# UKU100P.net
KiCad netlist of a schematic drawn in Altium Designer
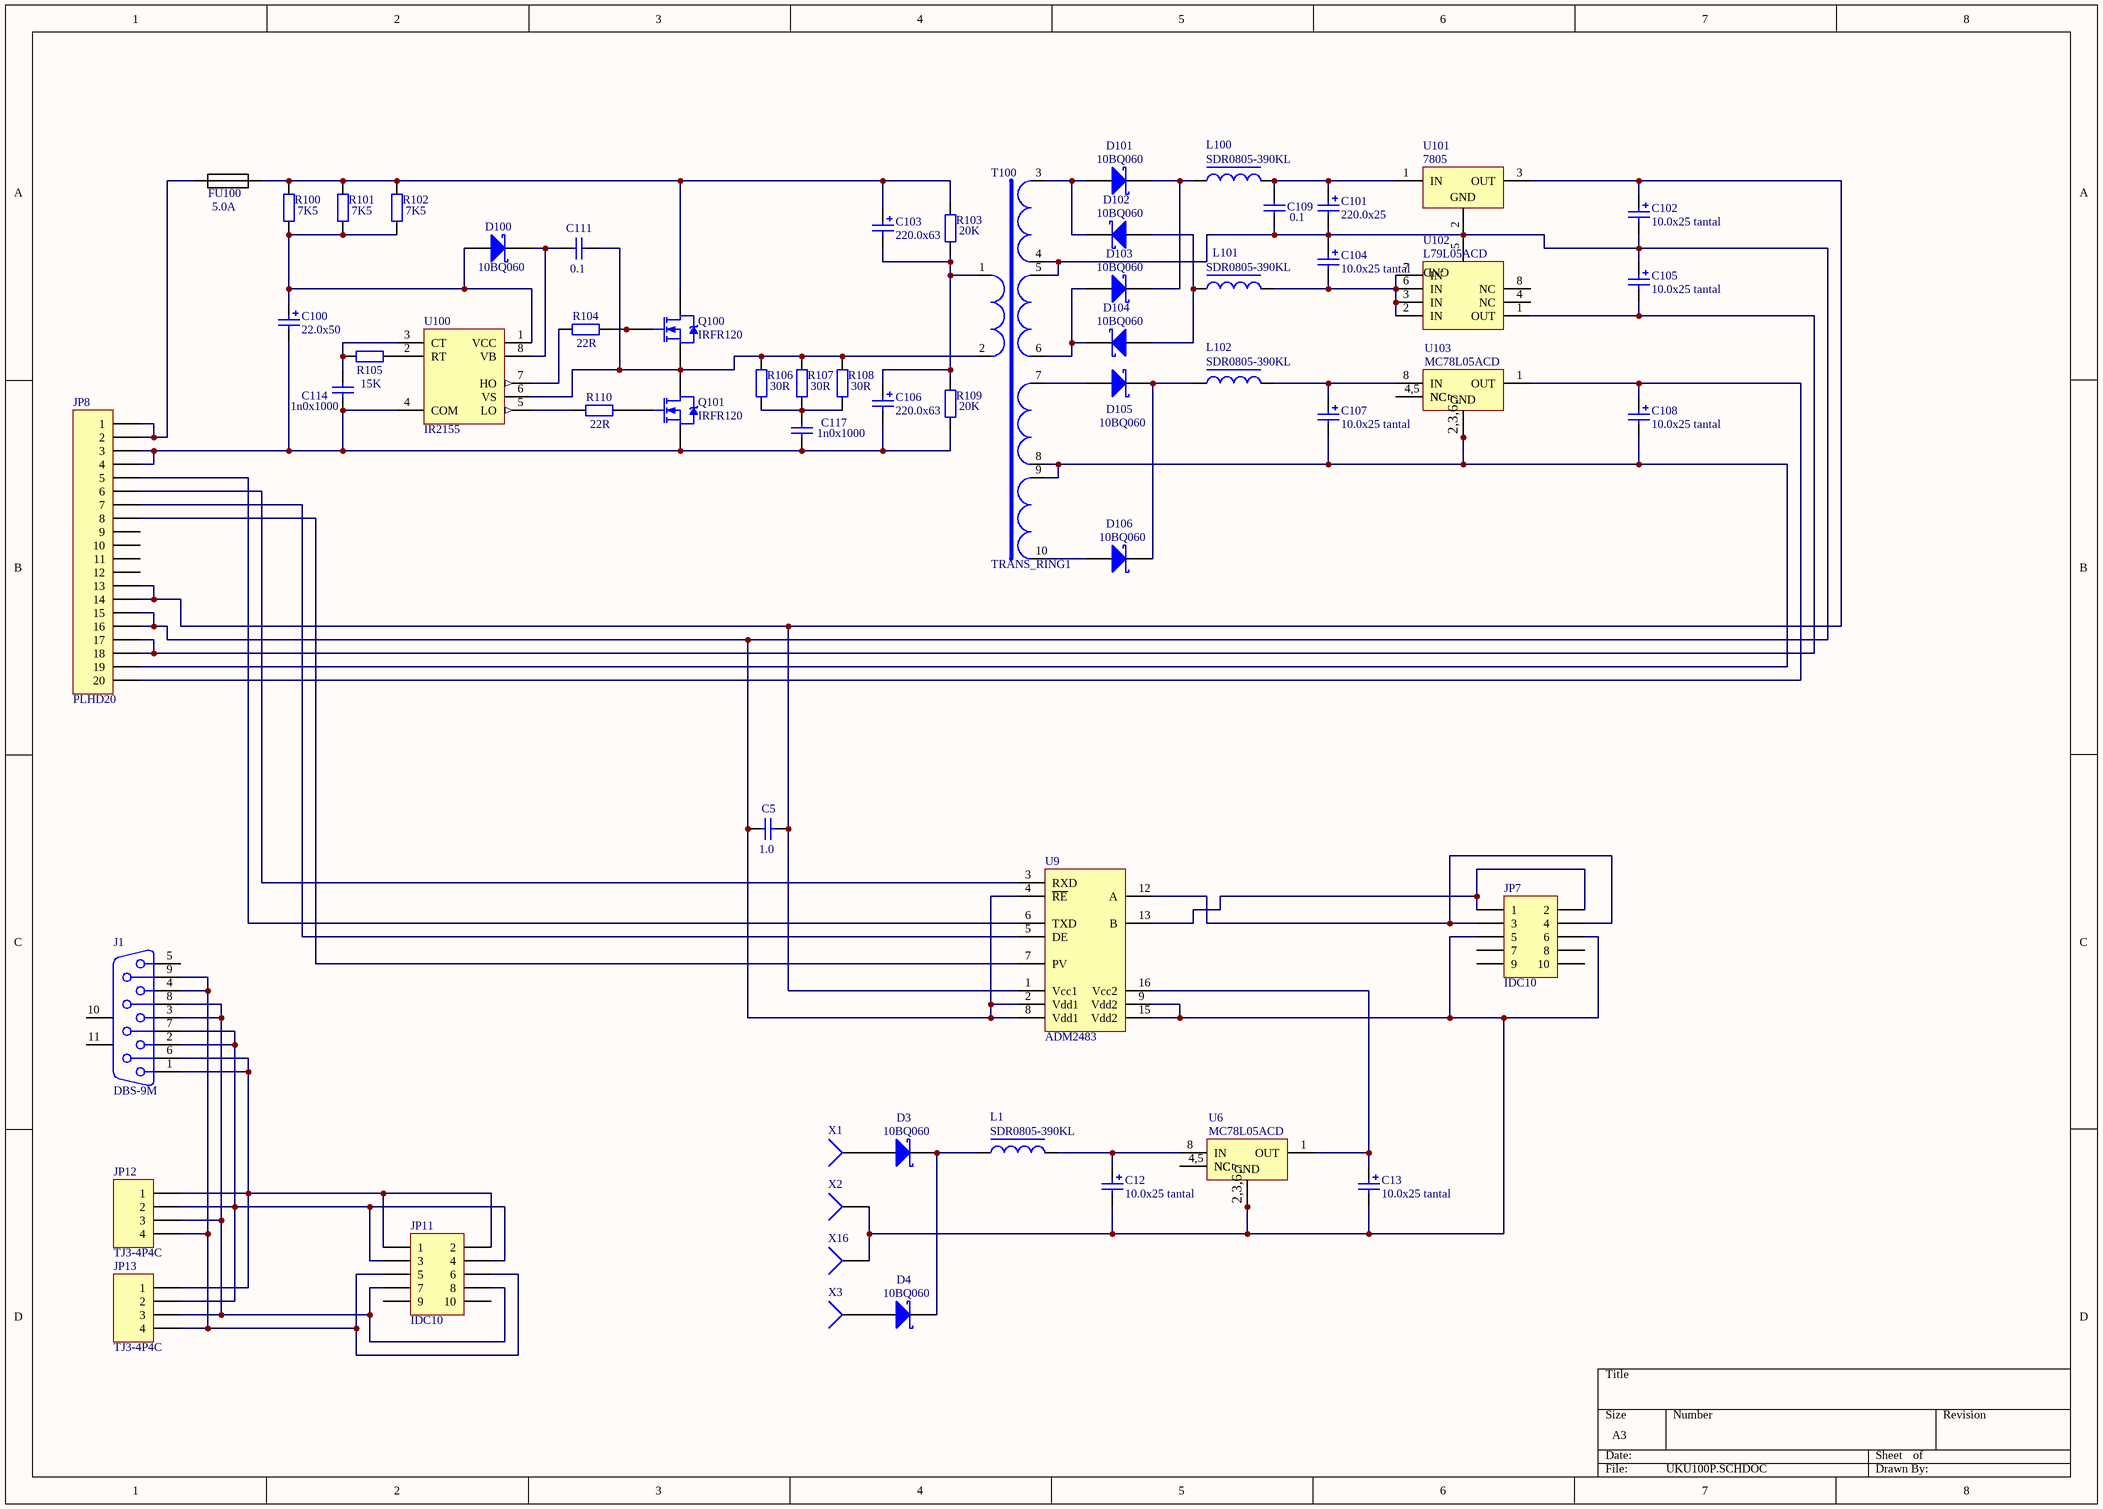
[diagram p0: UKU100P.SCHDOC]

(export (version "E")
  (design (tool "Eeschema 10.0.6"))
  (components
    (comp (ref "C5")
      (value "1.0")
      (footprint "C3216-1206")
      (description "Capacitor (Semiconductor SIM Model)")
      (fields (field (name "MANUFACTURER") "Generic Components") (field (name "PUBLISHER") "Altium Limited"))
      (libsource (lib "Miscellaneous Devices") (part "Cap Semi"))
    )
    (comp (ref "C12")
      (value "10.0x25 tantal")
      (footprint "CAP_EL_6_3")
      (description "Polarized Capacitor (Radial)")
      (fields (field (name "MANUFACTURER") "Generic Components") (field (name "PUBLISHER") "Altium Limited"))
      (libsource (lib "PAL") (part "Cap Pol1"))
    )
    (comp (ref "C13")
      (value "10.0x25 tantal")
      (footprint "CAP_EL_6_3")
      (description "Polarized Capacitor (Radial)")
      (fields (field (name "MANUFACTURER") "Generic Components") (field (name "PUBLISHER") "Altium Limited"))
      (libsource (lib "PAL") (part "Cap Pol1"))
    )
    (comp (ref "C100")
      (value "22.0x50")
      (footprint "el3")
      (description "Polarized Capacitor (Radial)")
      (fields (field (name "MANUFACTURER") "Generic Components") (field (name "PUBLISHER") "Altium Limited"))
      (libsource (lib "PAL") (part "Cap Pol1"))
    )
    (comp (ref "C101")
      (value "220.0x25")
      (footprint "el5")
      (description "Polarized Capacitor (Radial)")
      (fields (field (name "MANUFACTURER") "Generic Components") (field (name "PUBLISHER") "Altium Limited"))
      (libsource (lib "PAL") (part "Cap Pol1"))
    )
    (comp (ref "C102")
      (value "10.0x25 tantal")
      (footprint "CAP_EL_6_3")
      (description "Polarized Capacitor (Radial)")
      (fields (field (name "MANUFACTURER") "Generic Components") (field (name "PUBLISHER") "Altium Limited"))
      (libsource (lib "PAL") (part "Cap Pol1"))
    )
    (comp (ref "C103")
      (value "220.0x63")
      (footprint "el5")
      (description "Polarized Capacitor (Radial)")
      (fields (field (name "MANUFACTURER") "Generic Components") (field (name "PUBLISHER") "Altium Limited"))
      (libsource (lib "PAL") (part "Cap Pol1"))
    )
    (comp (ref "C104")
      (value "10.0x25 tantal")
      (footprint "CAP_EL_6_3")
      (description "Polarized Capacitor (Radial)")
      (fields (field (name "MANUFACTURER") "Generic Components") (field (name "PUBLISHER") "Altium Limited"))
      (libsource (lib "PAL") (part "Cap Pol1"))
    )
    (comp (ref "C105")
      (value "10.0x25 tantal")
      (footprint "CAP_EL_6_3")
      (description "Polarized Capacitor (Radial)")
      (fields (field (name "MANUFACTURER") "Generic Components") (field (name "PUBLISHER") "Altium Limited"))
      (libsource (lib "PAL") (part "Cap Pol1"))
    )
    (comp (ref "C106")
      (value "220.0x63")
      (footprint "el5")
      (description "Polarized Capacitor (Radial)")
      (fields (field (name "MANUFACTURER") "Generic Components") (field (name "PUBLISHER") "Altium Limited"))
      (libsource (lib "PAL") (part "Cap Pol1"))
    )
    (comp (ref "C107")
      (value "10.0x25 tantal")
      (footprint "CAP_EL_6_3")
      (description "Polarized Capacitor (Radial)")
      (fields (field (name "MANUFACTURER") "Generic Components") (field (name "PUBLISHER") "Altium Limited"))
      (libsource (lib "PAL") (part "Cap Pol1"))
    )
    (comp (ref "C108")
      (value "10.0x25 tantal")
      (footprint "CAP_EL_6_3")
      (description "Polarized Capacitor (Radial)")
      (fields (field (name "MANUFACTURER") "Generic Components") (field (name "PUBLISHER") "Altium Limited"))
      (libsource (lib "PAL") (part "Cap Pol1"))
    )
    (comp (ref "C109")
      (value "0.1")
      (footprint "C3216-1206")
      (description "Capacitor (Semiconductor SIM Model)")
      (fields (field (name "MANUFACTURER") "Generic Components") (field (name "PUBLISHER") "Altium Limited"))
      (libsource (lib "Miscellaneous Devices") (part "Cap Semi"))
    )
    (comp (ref "C111")
      (value "0.1")
      (footprint "C3216-1206")
      (description "Capacitor (Semiconductor SIM Model)")
      (fields (field (name "MANUFACTURER") "Generic Components") (field (name "PUBLISHER") "Altium Limited"))
      (libsource (lib "Miscellaneous Devices") (part "Cap Semi"))
    )
    (comp (ref "C114")
      (value "1n0x1000")
      (footprint "C3216-1206")
      (description "Capacitor (Semiconductor SIM Model)")
      (fields (field (name "MANUFACTURER") "Generic Components") (field (name "PUBLISHER") "Altium Limited"))
      (libsource (lib "Miscellaneous Devices") (part "Cap Semi"))
    )
    (comp (ref "C117")
      (value "1n0x1000")
      (footprint "C3216-1206")
      (description "Capacitor (Semiconductor SIM Model)")
      (fields (field (name "MANUFACTURER") "Generic Components") (field (name "PUBLISHER") "Altium Limited"))
      (libsource (lib "Miscellaneous Devices") (part "Cap Semi"))
    )
    (comp (ref "D3")
      (value "10BQ060")
      (footprint "DSO-C2/X2.3")
      (description "Schottky Rectifier")
      (fields
        (field (name "MANUFACTURER") "International Rectifier")
        (field (name "PUBLISHER") "Altium Limited")
      )
      (libsource (lib "IR Discrete Diode") (part "10BQ015"))
    )
    (comp (ref "D4")
      (value "10BQ060")
      (footprint "DSO-C2/X2.3")
      (description "Schottky Rectifier")
      (fields
        (field (name "MANUFACTURER") "International Rectifier")
        (field (name "PUBLISHER") "Altium Limited")
      )
      (libsource (lib "IR Discrete Diode") (part "10BQ015"))
    )
    (comp (ref "D100")
      (value "10BQ060")
      (footprint "DSO-C2/X2.3")
      (description "Schottky Rectifier")
      (fields
        (field (name "MANUFACTURER") "International Rectifier")
        (field (name "PUBLISHER") "Altium Limited")
      )
      (libsource (lib "IR Discrete Diode") (part "10BQ015"))
    )
    (comp (ref "D101")
      (value "10BQ060")
      (footprint "D_6_3")
      (description "Schottky Rectifier")
      (fields
        (field (name "MANUFACTURER") "International Rectifier")
        (field (name "PUBLISHER") "Altium Limited")
      )
      (libsource (lib "IR Discrete Diode") (part "10BQ015"))
    )
    (comp (ref "D102")
      (value "10BQ060")
      (footprint "D_6_3")
      (description "Schottky Rectifier")
      (fields
        (field (name "MANUFACTURER") "International Rectifier")
        (field (name "PUBLISHER") "Altium Limited")
      )
      (libsource (lib "IR Discrete Diode") (part "10BQ015"))
    )
    (comp (ref "D103")
      (value "10BQ060")
      (footprint "D_6_3")
      (description "Schottky Rectifier")
      (fields
        (field (name "MANUFACTURER") "International Rectifier")
        (field (name "PUBLISHER") "Altium Limited")
      )
      (libsource (lib "IR Discrete Diode") (part "10BQ015"))
    )
    (comp (ref "D104")
      (value "10BQ060")
      (footprint "D_6_3")
      (description "Schottky Rectifier")
      (fields
        (field (name "MANUFACTURER") "International Rectifier")
        (field (name "PUBLISHER") "Altium Limited")
      )
      (libsource (lib "IR Discrete Diode") (part "10BQ015"))
    )
    (comp (ref "D105")
      (value "10BQ060")
      (footprint "DSO-C2/X2.3")
      (description "Schottky Rectifier")
      (fields
        (field (name "MANUFACTURER") "International Rectifier")
        (field (name "PUBLISHER") "Altium Limited")
      )
      (libsource (lib "IR Discrete Diode") (part "10BQ015"))
    )
    (comp (ref "D106")
      (value "10BQ060")
      (footprint "DSO-C2/X2.3")
      (description "Schottky Rectifier")
      (fields
        (field (name "MANUFACTURER") "International Rectifier")
        (field (name "PUBLISHER") "Altium Limited")
      )
      (libsource (lib "IR Discrete Diode") (part "10BQ015"))
    )
    (comp (ref "FU100") (value "5.0A") (footprint "FUSE2") (libsource (lib "PAL") (part "FUSE")))
    (comp (ref "J1")
      (value "DBS-9M")
      (footprint "DSUB_N9")
      (description "Receptacle Assembly, 9 Position, Right Angle")
      (fields (field (name "MANUFACTURER") "Generic Components") (field (name "PUBLISHER") "Altium Limited"))
      (libsource (lib "Miscellaneous Connectors") (part "D Connector 9"))
    )
    (comp (ref "JP7")
      (value "IDC10")
      (footprint "HDR2X5")
      (description "Header, 5-Pin, Dual row")
      (fields (field (name "MANUFACTURER") "Generic Components") (field (name "PUBLISHER") "Altium Limited"))
      (libsource (lib "Miscellaneous Connectors") (part "Header 5X2"))
    )
    (comp (ref "JP8")
      (value "PLHD20")
      (footprint "HDR2X10")
      (description "Header, 20-Pin")
      (fields (field (name "MANUFACTURER") "Generic Components") (field (name "PUBLISHER") "Altium Limited"))
      (libsource (lib "Miscellaneous Connectors") (part "Header 20"))
    )
    (comp (ref "JP11")
      (value "IDC10")
      (footprint "HDR2X5")
      (description "Header, 5-Pin, Dual row")
      (fields (field (name "MANUFACTURER") "Generic Components") (field (name "PUBLISHER") "Altium Limited"))
      (libsource (lib "Miscellaneous Connectors") (part "Header 5X2"))
    )
    (comp (ref "JP12")
      (value "TJ3-4P4C")
      (footprint "tj3-4p4c")
      (description "Header, 4-Pin")
      (fields (field (name "MANUFACTURER") "Generic Components") (field (name "PUBLISHER") "Altium Limited"))
      (libsource (lib "Miscellaneous Connectors") (part "Header 4"))
    )
    (comp (ref "JP13")
      (value "TJ3-4P4C")
      (footprint "tj3-4p4c")
      (description "Header, 4-Pin")
      (fields (field (name "MANUFACTURER") "Generic Components") (field (name "PUBLISHER") "Altium Limited"))
      (libsource (lib "Miscellaneous Connectors") (part "Header 4"))
    )
    (comp (ref "L1")
      (value "SDR0805-390KL")
      (footprint "L10x10")
      (description "Magnetic-Core Inductor")
      (fields (field (name "MANUFACTURER") "Generic Components") (field (name "PUBLISHER") "Altium Limited"))
      (libsource (lib "PAL") (part "Inductor Konstr 2"))
    )
    (comp (ref "L100")
      (value "SDR0805-390KL")
      (footprint "L10x10")
      (description "Magnetic-Core Inductor")
      (fields (field (name "MANUFACTURER") "Generic Components") (field (name "PUBLISHER") "Altium Limited"))
      (libsource (lib "PAL") (part "Inductor Konstr 2"))
    )
    (comp (ref "L101")
      (value "SDR0805-390KL")
      (footprint "L10x10")
      (description "Magnetic-Core Inductor")
      (fields (field (name "MANUFACTURER") "Generic Components") (field (name "PUBLISHER") "Altium Limited"))
      (libsource (lib "PAL") (part "Inductor Konstr 2"))
    )
    (comp (ref "L102")
      (value "SDR0805-390KL")
      (footprint "L10x10")
      (description "Magnetic-Core Inductor")
      (fields (field (name "MANUFACTURER") "Generic Components") (field (name "PUBLISHER") "Altium Limited"))
      (libsource (lib "PAL") (part "Inductor Konstr 2"))
    )
    (comp (ref "Q100")
      (value "IRFR120")
      (footprint "SIP-G3/E8")
      (description "HEXFET N-Channel Power MOSFET")
      (fields
        (field (name "MANUFACTURER") "International Rectifier")
        (field (name "PUBLISHER") "Altium Limited")
      )
      (libsource (lib "IR Discrete MOSFET") (part "IRFR120"))
    )
    (comp (ref "Q101")
      (value "IRFR120")
      (footprint "SIP-G3/E8")
      (description "HEXFET N-Channel Power MOSFET")
      (fields
        (field (name "MANUFACTURER") "International Rectifier")
        (field (name "PUBLISHER") "Altium Limited")
      )
      (libsource (lib "IR Discrete MOSFET") (part "IRFR120"))
    )
    (comp (ref "R100")
      (value "7K5")
      (footprint "_1206")
      (description "Resistor")
      (fields (field (name "MANUFACTURER") "Generic Components") (field (name "PUBLISHER") "Altium Limited"))
      (libsource (lib "") (part "Res2_1"))
    )
    (comp (ref "R101")
      (value "7K5")
      (footprint "_1206")
      (description "Resistor")
      (fields (field (name "MANUFACTURER") "Generic Components") (field (name "PUBLISHER") "Altium Limited"))
      (libsource (lib "") (part "Res2_1"))
    )
    (comp (ref "R102")
      (value "7K5")
      (footprint "_1206")
      (description "Resistor")
      (fields (field (name "MANUFACTURER") "Generic Components") (field (name "PUBLISHER") "Altium Limited"))
      (libsource (lib "") (part "Res2_1"))
    )
    (comp (ref "R103")
      (value "20K")
      (footprint "_1206")
      (description "Resistor")
      (fields (field (name "MANUFACTURER") "Generic Components") (field (name "PUBLISHER") "Altium Limited"))
      (libsource (lib "") (part "Res2_1"))
    )
    (comp (ref "R104")
      (value "22R")
      (footprint "_1206")
      (description "Resistor")
      (fields (field (name "MANUFACTURER") "Generic Components") (field (name "PUBLISHER") "Altium Limited"))
      (libsource (lib "Miscellaneous Devices") (part "Res2"))
    )
    (comp (ref "R105")
      (value "15K")
      (footprint "_1206")
      (description "Resistor")
      (fields (field (name "MANUFACTURER") "Generic Components") (field (name "PUBLISHER") "Altium Limited"))
      (libsource (lib "Miscellaneous Devices") (part "Res2"))
    )
    (comp (ref "R106")
      (value "30R")
      (footprint "_1206")
      (description "Resistor")
      (fields (field (name "MANUFACTURER") "Generic Components") (field (name "PUBLISHER") "Altium Limited"))
      (libsource (lib "") (part "Res2_1"))
    )
    (comp (ref "R107")
      (value "30R")
      (footprint "_1206")
      (description "Resistor")
      (fields (field (name "MANUFACTURER") "Generic Components") (field (name "PUBLISHER") "Altium Limited"))
      (libsource (lib "") (part "Res2_1"))
    )
    (comp (ref "R108")
      (value "30R")
      (footprint "_1206")
      (description "Resistor")
      (fields (field (name "MANUFACTURER") "Generic Components") (field (name "PUBLISHER") "Altium Limited"))
      (libsource (lib "") (part "Res2_1"))
    )
    (comp (ref "R109")
      (value "20K")
      (footprint "_1206")
      (description "Resistor")
      (fields (field (name "MANUFACTURER") "Generic Components") (field (name "PUBLISHER") "Altium Limited"))
      (libsource (lib "") (part "Res2_1"))
    )
    (comp (ref "R110")
      (value "22R")
      (footprint "_1206")
      (description "Resistor")
      (fields (field (name "MANUFACTURER") "Generic Components") (field (name "PUBLISHER") "Altium Limited"))
      (libsource (lib "Miscellaneous Devices") (part "Res2"))
    )
    (comp (ref "T100")
      (value "TRANS_RING1")
      (footprint "trans_ring1")
      (libsource (lib "PAL") (part "TRANS_RING1"))
    )
    (comp (ref "U6")
      (value "MC78L05ACD")
      (footprint "SO-G8")
      (description "3-Terminal Low-Current Positive Fixed Voltage Regulator")
      (fields (field (name "MANUFACTURER") "Motorola") (field (name "PUBLISHER") "Altium Limited"))
      (libsource (lib "Motorola Power Management Voltage Regulator") (part "MC78L05ACD"))
    )
    (comp (ref "U9") (value "ADM2483") (footprint "SO-G16/D10.4") (libsource (lib "PAL") (part "ADM2483")))
    (comp (ref "U100")
      (value "IR2155")
      (footprint "DIP-8/D11")
      (description "Self-Oscillating Half-Bridge Driver")
      (fields
        (field (name "MANUFACTURER") "International Rectifier")
        (field (name "PUBLISHER") "Altium Limited")
      )
      (libsource (lib "IR Interface Bridge Driver") (part "IR2155"))
    )
    (comp (ref "U101")
      (value "7805")
      (footprint "7805_1")
      (description "3-Terminal Positive Fixed Voltage Regulator")
      (fields (field (name "MANUFACTURER") "Motorola") (field (name "PUBLISHER") "Altium Limited"))
      (libsource (lib "PAL") (part "7805"))
    )
    (comp (ref "U102")
      (value "L79L05ACD")
      (footprint "SO-G8")
      (description "Negative Voltage Regulator")
      (fields (field (name "MANUFACTURER") "ST-Microelectronics") (field (name "PUBLISHER") "Altium Limited"))
      (libsource (lib "ST Power Mgt Voltage Regulator") (part "L79L05ACD"))
    )
    (comp (ref "U103")
      (value "MC78L05ACD")
      (footprint "SO-G8")
      (description "3-Terminal Low-Current Positive Fixed Voltage Regulator")
      (fields (field (name "MANUFACTURER") "Motorola") (field (name "PUBLISHER") "Altium Limited"))
      (libsource (lib "Motorola Power Management Voltage Regulator") (part "MC78L05ACD"))
    )
    (comp (ref "X1")
      (value "~")
      (footprint "PIN1")
      (description "Socket")
      (fields (field (name "MANUFACTURER") "Generic Components") (field (name "PUBLISHER") "Altium Limited"))
      (libsource (lib "Miscellaneous Connectors") (part "Socket"))
    )
    (comp (ref "X2")
      (value "~")
      (footprint "PIN1")
      (description "Socket")
      (fields (field (name "MANUFACTURER") "Generic Components") (field (name "PUBLISHER") "Altium Limited"))
      (libsource (lib "Miscellaneous Connectors") (part "Socket"))
    )
    (comp (ref "X3")
      (value "~")
      (footprint "PIN1")
      (description "Socket")
      (fields (field (name "MANUFACTURER") "Generic Components") (field (name "PUBLISHER") "Altium Limited"))
      (libsource (lib "Miscellaneous Connectors") (part "Socket"))
    )
    (comp (ref "X16")
      (value "~")
      (footprint "PIN1")
      (description "Socket")
      (fields (field (name "MANUFACTURER") "Generic Components") (field (name "PUBLISHER") "Altium Limited"))
      (libsource (lib "Miscellaneous Connectors") (part "Socket"))
    )
  )
  (nets
    (net (code "1") (name "Net-(C12-Pad2)") (class "Default")
      (node (ref "C12") (pin "2") (pinfunction "2_2") (pintype "passive"))
      (node (ref "C13") (pin "2") (pinfunction "2_2") (pintype "passive"))
      (node (ref "JP7") (pin "5") (pinfunction "5_5") (pintype "passive"))
      (node (ref "JP7") (pin "6") (pinfunction "6_6") (pintype "passive"))
      (node (ref "U6") (pin "2") (pinfunction "GND_2") (pintype "power_in"))
      (node (ref "U6") (pin "3") (pinfunction "GND_3") (pintype "power_in"))
      (node (ref "U6") (pin "6") (pinfunction "GND_6") (pintype "power_in"))
      (node (ref "U6") (pin "7") (pinfunction "GND_7") (pintype "power_in"))
      (node (ref "U9") (pin "15") (pinfunction "Vdd2_15") (pintype "passive"))
      (node (ref "U9") (pin "9") (pinfunction "Vdd2_9") (pintype "passive"))
      (node (ref "X16") (pin "1") (pinfunction "1_1") (pintype "passive"))
      (node (ref "X2") (pin "1") (pinfunction "1_1") (pintype "passive"))
    )
    (net (code "2") (name "Net-(C103-Pad2)") (class "Default")
      (node (ref "C103") (pin "2") (pinfunction "2_2") (pintype "passive"))
      (node (ref "C106") (pin "1") (pinfunction "1_1") (pintype "passive"))
      (node (ref "R103") (pin "2") (pinfunction "2_2") (pintype "passive"))
      (node (ref "R109") (pin "1") (pinfunction "1_1") (pintype "passive"))
      (node (ref "T100") (pin "1") (pinfunction "Vss_1") (pintype "passive"))
    )
    (net (code "3") (name "Net-(C104-Pad2)") (class "Default")
      (node (ref "C104") (pin "2") (pinfunction "2_2") (pintype "passive"))
      (node (ref "L101") (pin "2") (pinfunction "2_2") (pintype "passive"))
      (node (ref "U102") (pin "2") (pinfunction "IN_2") (pintype "power_in"))
      (node (ref "U102") (pin "3") (pinfunction "IN_3") (pintype "power_in"))
      (node (ref "U102") (pin "6") (pinfunction "IN_6") (pintype "power_in"))
      (node (ref "U102") (pin "7") (pinfunction "IN_7") (pintype "power_in"))
    )
    (net (code "4") (name "Net-(C107-Pad2)") (class "Default")
      (node (ref "C107") (pin "2") (pinfunction "2_2") (pintype "passive"))
      (node (ref "C108") (pin "2") (pinfunction "2_2") (pintype "passive"))
      (node (ref "JP8") (pin "19") (pinfunction "19_19") (pintype "passive"))
      (node (ref "T100") (pin "8") (pinfunction "Vss_8") (pintype "passive"))
      (node (ref "T100") (pin "9") (pinfunction "Vss_9") (pintype "passive"))
      (node (ref "U103") (pin "2") (pinfunction "GND_2") (pintype "power_in"))
      (node (ref "U103") (pin "3") (pinfunction "GND_3") (pintype "power_in"))
      (node (ref "U103") (pin "6") (pinfunction "GND_6") (pintype "power_in"))
      (node (ref "U103") (pin "7") (pinfunction "GND_7") (pintype "power_in"))
    )
    (net (code "5") (name "Net-(C117-Pad1)") (class "Default")
      (node (ref "C117") (pin "1") (pinfunction "1_1") (pintype "passive"))
      (node (ref "R106") (pin "2") (pinfunction "2_2") (pintype "passive"))
      (node (ref "R107") (pin "2") (pinfunction "2_2") (pintype "passive"))
      (node (ref "R108") (pin "2") (pinfunction "2_2") (pintype "passive"))
    )
    (net (code "6") (name "Net-(D3-A)") (class "Default")
      (node (ref "D3") (pin "1") (pinfunction "A_1") (pintype "passive"))
      (node (ref "X1") (pin "1") (pinfunction "1_1") (pintype "passive"))
    )
    (net (code "7") (name "Net-(D3-K)") (class "Default")
      (node (ref "D3") (pin "2") (pinfunction "K_2") (pintype "passive"))
      (node (ref "D4") (pin "2") (pinfunction "K_2") (pintype "passive"))
      (node (ref "L1") (pin "1") (pinfunction "1_1") (pintype "passive"))
    )
    (net (code "8") (name "Net-(D4-A)") (class "Default")
      (node (ref "D4") (pin "1") (pinfunction "A_1") (pintype "passive"))
      (node (ref "X3") (pin "1") (pinfunction "1_1") (pintype "passive"))
    )
    (net (code "9") (name "Net-(D100-A)") (class "Default")
      (node (ref "C100") (pin "1") (pinfunction "1_1") (pintype "passive"))
      (node (ref "D100") (pin "1") (pinfunction "A_1") (pintype "passive"))
      (node (ref "R100") (pin "2") (pinfunction "2_2") (pintype "passive"))
      (node (ref "R101") (pin "2") (pinfunction "2_2") (pintype "passive"))
      (node (ref "R102") (pin "2") (pinfunction "2_2") (pintype "passive"))
      (node (ref "U100") (pin "1") (pinfunction "VCC_1") (pintype "power_in"))
    )
    (net (code "10") (name "Net-(D100-K)") (class "Default")
      (node (ref "C111") (pin "1") (pinfunction "1_1") (pintype "passive"))
      (node (ref "D100") (pin "2") (pinfunction "K_2") (pintype "passive"))
      (node (ref "U100") (pin "8") (pinfunction "VB_8") (pintype "power_in"))
    )
    (net (code "11") (name "Net-(D101-A)") (class "Default")
      (node (ref "D101") (pin "1") (pinfunction "A_1") (pintype "passive"))
      (node (ref "D102") (pin "2") (pinfunction "K_2") (pintype "passive"))
      (node (ref "T100") (pin "3") (pinfunction "Vss_3") (pintype "passive"))
    )
    (net (code "12") (name "Net-(D101-K)") (class "Default")
      (node (ref "D101") (pin "2") (pinfunction "K_2") (pintype "passive"))
      (node (ref "D103") (pin "2") (pinfunction "K_2") (pintype "passive"))
      (node (ref "L100") (pin "1") (pinfunction "1_1") (pintype "passive"))
    )
    (net (code "13") (name "Net-(D102-A)") (class "Default")
      (node (ref "D102") (pin "1") (pinfunction "A_1") (pintype "passive"))
      (node (ref "D104") (pin "1") (pinfunction "A_1") (pintype "passive"))
      (node (ref "L101") (pin "1") (pinfunction "1_1") (pintype "passive"))
    )
    (net (code "14") (name "Net-(D103-A)") (class "Default")
      (node (ref "D103") (pin "1") (pinfunction "A_1") (pintype "passive"))
      (node (ref "D104") (pin "2") (pinfunction "K_2") (pintype "passive"))
      (node (ref "T100") (pin "6") (pinfunction "Vss_6") (pintype "passive"))
    )
    (net (code "15") (name "Net-(D105-A)") (class "Default")
      (node (ref "D105") (pin "1") (pinfunction "A_1") (pintype "passive"))
      (node (ref "T100") (pin "7") (pinfunction "Vss_7") (pintype "passive"))
    )
    (net (code "16") (name "Net-(D105-K)") (class "Default")
      (node (ref "D105") (pin "2") (pinfunction "K_2") (pintype "passive"))
      (node (ref "D106") (pin "2") (pinfunction "K_2") (pintype "passive"))
      (node (ref "L102") (pin "1") (pinfunction "1_1") (pintype "passive"))
    )
    (net (code "17") (name "Net-(D106-A)") (class "Default")
      (node (ref "D106") (pin "1") (pinfunction "A_1") (pintype "passive"))
      (node (ref "T100") (pin "10") (pinfunction "Vss_10") (pintype "passive"))
    )
    (net (code "18") (name "Net-(FU100-Pad1)") (class "Default")
      (node (ref "FU100") (pin "1") (pinfunction "1_1") (pintype "passive"))
      (node (ref "JP8") (pin "1") (pinfunction "1_1") (pintype "passive"))
      (node (ref "JP8") (pin "2") (pinfunction "2_2") (pintype "passive"))
    )
    (net (code "19") (name "Net-(J1-Pad1)") (class "Default")
      (node (ref "J1") (pin "1") (pinfunction "1_1") (pintype "passive"))
      (node (ref "J1") (pin "6") (pinfunction "6_6") (pintype "passive"))
      (node (ref "JP11") (pin "1") (pinfunction "1_1") (pintype "passive"))
      (node (ref "JP11") (pin "2") (pinfunction "2_2") (pintype "passive"))
      (node (ref "JP12") (pin "1") (pinfunction "1_1") (pintype "passive"))
      (node (ref "JP13") (pin "1") (pinfunction "1_1") (pintype "passive"))
    )
    (net (code "20") (name "Net-(J1-Pad2)") (class "Default")
      (node (ref "J1") (pin "2") (pinfunction "2_2") (pintype "passive"))
      (node (ref "J1") (pin "7") (pinfunction "7_7") (pintype "passive"))
      (node (ref "JP11") (pin "3") (pinfunction "3_3") (pintype "passive"))
      (node (ref "JP11") (pin "4") (pinfunction "4_4") (pintype "passive"))
      (node (ref "JP12") (pin "2") (pinfunction "2_2") (pintype "passive"))
      (node (ref "JP13") (pin "2") (pinfunction "2_2") (pintype "passive"))
    )
    (net (code "21") (name "Net-(J1-Pad3)") (class "Default")
      (node (ref "J1") (pin "3") (pinfunction "3_3") (pintype "passive"))
      (node (ref "J1") (pin "8") (pinfunction "8_8") (pintype "passive"))
      (node (ref "JP11") (pin "7") (pinfunction "7_7") (pintype "passive"))
      (node (ref "JP11") (pin "8") (pinfunction "8_8") (pintype "passive"))
      (node (ref "JP12") (pin "3") (pinfunction "3_3") (pintype "passive"))
      (node (ref "JP13") (pin "3") (pinfunction "3_3") (pintype "passive"))
    )
    (net (code "22") (name "Net-(J1-Pad4)") (class "Default")
      (node (ref "J1") (pin "4") (pinfunction "4_4") (pintype "passive"))
      (node (ref "J1") (pin "9") (pinfunction "9_9") (pintype "passive"))
      (node (ref "JP11") (pin "5") (pinfunction "5_5") (pintype "passive"))
      (node (ref "JP11") (pin "6") (pinfunction "6_6") (pintype "passive"))
      (node (ref "JP12") (pin "4") (pinfunction "4_4") (pintype "passive"))
      (node (ref "JP13") (pin "4") (pinfunction "4_4") (pintype "passive"))
    )
    (net (code "23") (name "Net-(Q100-D)") (class "Default")
      (node (ref "C103") (pin "1") (pinfunction "1_1") (pintype "passive"))
      (node (ref "FU100") (pin "2") (pinfunction "2_2") (pintype "passive"))
      (node (ref "Q100") (pin "4") (pinfunction "D_4") (pintype "passive"))
      (node (ref "R100") (pin "1") (pinfunction "1_1") (pintype "passive"))
      (node (ref "R101") (pin "1") (pinfunction "1_1") (pintype "passive"))
      (node (ref "R102") (pin "1") (pinfunction "1_1") (pintype "passive"))
      (node (ref "R103") (pin "1") (pinfunction "1_1") (pintype "passive"))
    )
    (net (code "24") (name "Net-(Q100-G)") (class "Default")
      (node (ref "Q100") (pin "1") (pinfunction "G_1") (pintype "passive"))
      (node (ref "R104") (pin "2") (pinfunction "2_2") (pintype "passive"))
    )
    (net (code "25") (name "Net-(Q100-S)") (class "Default")
      (node (ref "C111") (pin "2") (pinfunction "2_2") (pintype "passive"))
      (node (ref "Q100") (pin "3") (pinfunction "S_3") (pintype "passive"))
      (node (ref "Q101") (pin "4") (pinfunction "D_4") (pintype "passive"))
      (node (ref "R106") (pin "1") (pinfunction "1_1") (pintype "passive"))
      (node (ref "R107") (pin "1") (pinfunction "1_1") (pintype "passive"))
      (node (ref "R108") (pin "1") (pinfunction "1_1") (pintype "passive"))
      (node (ref "T100") (pin "2") (pinfunction "Vss_2") (pintype "passive"))
      (node (ref "U100") (pin "6") (pinfunction "VS_6") (pintype "power_in"))
    )
    (net (code "26") (name "Net-(Q101-G)") (class "Default")
      (node (ref "Q101") (pin "1") (pinfunction "G_1") (pintype "passive"))
      (node (ref "R110") (pin "2") (pinfunction "2_2") (pintype "passive"))
    )
    (net (code "27") (name "Net-(Q101-S)") (class "Default")
      (node (ref "C100") (pin "2") (pinfunction "2_2") (pintype "passive"))
      (node (ref "C106") (pin "2") (pinfunction "2_2") (pintype "passive"))
      (node (ref "C114") (pin "2") (pinfunction "2_2") (pintype "passive"))
      (node (ref "C117") (pin "2") (pinfunction "2_2") (pintype "passive"))
      (node (ref "JP8") (pin "3") (pinfunction "3_3") (pintype "passive"))
      (node (ref "JP8") (pin "4") (pinfunction "4_4") (pintype "passive"))
      (node (ref "Q101") (pin "3") (pinfunction "S_3") (pintype "passive"))
      (node (ref "R109") (pin "2") (pinfunction "2_2") (pintype "passive"))
      (node (ref "U100") (pin "4") (pinfunction "COM_4") (pintype "power_in"))
    )
    (net (code "28") (name "Net-(U6-IN)") (class "Default")
      (node (ref "C12") (pin "1") (pinfunction "1_1") (pintype "passive"))
      (node (ref "L1") (pin "2") (pinfunction "2_2") (pintype "passive"))
      (node (ref "U6") (pin "8") (pinfunction "IN_8") (pintype "power_in"))
    )
    (net (code "29") (name "Net-(U6-NC-Pad4)") (class "Default")
      (node (ref "U6") (pin "4") (pinfunction "NC_4") (pintype "passive"))
      (node (ref "U6") (pin "5") (pinfunction "NC_5") (pintype "passive"))
    )
    (net (code "30") (name "Net-(U6-OUT)") (class "Default")
      (node (ref "C13") (pin "1") (pinfunction "1_1") (pintype "passive"))
      (node (ref "U6") (pin "1") (pinfunction "OUT_1") (pintype "power_in"))
      (node (ref "U9") (pin "16") (pinfunction "Vcc2_16") (pintype "passive"))
    )
    (net (code "31") (name "Net-(U9-A)") (class "Default")
      (node (ref "JP7") (pin "3") (pinfunction "3_3") (pintype "passive"))
      (node (ref "JP7") (pin "4") (pinfunction "4_4") (pintype "passive"))
      (node (ref "U9") (pin "12") (pinfunction "A_12") (pintype "passive"))
    )
    (net (code "32") (name "Net-(U9-B)") (class "Default")
      (node (ref "JP7") (pin "1") (pinfunction "1_1") (pintype "passive"))
      (node (ref "JP7") (pin "2") (pinfunction "2_2") (pintype "passive"))
      (node (ref "U9") (pin "13") (pinfunction "B_13") (pintype "passive"))
    )
    (net (code "33") (name "Net-(U9-DE)") (class "Default")
      (node (ref "JP8") (pin "7") (pinfunction "7_7") (pintype "passive"))
      (node (ref "U9") (pin "5") (pinfunction "DE_5") (pintype "passive"))
    )
    (net (code "34") (name "Net-(U9-PV)") (class "Default")
      (node (ref "JP8") (pin "8") (pinfunction "8_8") (pintype "passive"))
      (node (ref "U9") (pin "7") (pinfunction "PV_7") (pintype "passive"))
    )
    (net (code "35") (name "Net-(U9-RXD)") (class "Default")
      (node (ref "JP8") (pin "6") (pinfunction "6_6") (pintype "passive"))
      (node (ref "U9") (pin "3") (pinfunction "RXD_3") (pintype "passive"))
    )
    (net (code "36") (name "Net-(U9-TXD)") (class "Default")
      (node (ref "JP8") (pin "5") (pinfunction "5_5") (pintype "passive"))
      (node (ref "U9") (pin "6") (pinfunction "TXD_6") (pintype "passive"))
    )
    (net (code "37") (name "Net-(U100-CT)") (class "Default")
      (node (ref "C114") (pin "1") (pinfunction "1_1") (pintype "passive"))
      (node (ref "R105") (pin "1") (pinfunction "1_1") (pintype "passive"))
      (node (ref "U100") (pin "3") (pinfunction "CT_3") (pintype "passive"))
    )
    (net (code "38") (name "Net-(U100-HO)") (class "Default")
      (node (ref "R104") (pin "1") (pinfunction "1_1") (pintype "passive"))
      (node (ref "U100") (pin "7") (pinfunction "HO_7") (pintype "output"))
    )
    (net (code "39") (name "Net-(U100-LO)") (class "Default")
      (node (ref "R110") (pin "1") (pinfunction "1_1") (pintype "passive"))
      (node (ref "U100") (pin "5") (pinfunction "LO_5") (pintype "output"))
    )
    (net (code "40") (name "Net-(U100-RT)") (class "Default")
      (node (ref "R105") (pin "2") (pinfunction "2_2") (pintype "passive"))
      (node (ref "U100") (pin "2") (pinfunction "RT_2") (pintype "passive"))
    )
    (net (code "41") (name "Net-(U101-GND)") (class "Default")
      (node (ref "C101") (pin "2") (pinfunction "2_2") (pintype "passive"))
      (node (ref "C102") (pin "2") (pinfunction "2_2") (pintype "passive"))
      (node (ref "C104") (pin "1") (pinfunction "1_1") (pintype "passive"))
      (node (ref "C105") (pin "1") (pinfunction "1_1") (pintype "passive"))
      (node (ref "C109") (pin "1") (pinfunction "1_1") (pintype "passive"))
      (node (ref "C5") (pin "2") (pinfunction "2_2") (pintype "passive"))
      (node (ref "JP8") (pin "15") (pinfunction "15_15") (pintype "passive"))
      (node (ref "JP8") (pin "16") (pinfunction "16_16") (pintype "passive"))
      (node (ref "T100") (pin "4") (pinfunction "Vss_4") (pintype "passive"))
      (node (ref "T100") (pin "5") (pinfunction "Vss_5") (pintype "passive"))
      (node (ref "U101") (pin "2") (pinfunction "GND_2") (pintype "power_in"))
      (node (ref "U102") (pin "5") (pinfunction "GND_5") (pintype "power_in"))
      (node (ref "U9") (pin "2") (pinfunction "Vdd1_2") (pintype "passive"))
      (node (ref "U9") (pin "4") (pinfunction "~{RE}_4") (pintype "passive"))
      (node (ref "U9") (pin "8") (pinfunction "Vdd1_8") (pintype "passive"))
    )
    (net (code "42") (name "Net-(U101-IN)") (class "Default")
      (node (ref "C101") (pin "1") (pinfunction "1_1") (pintype "passive"))
      (node (ref "C109") (pin "2") (pinfunction "2_2") (pintype "passive"))
      (node (ref "L100") (pin "2") (pinfunction "2_2") (pintype "passive"))
      (node (ref "U101") (pin "1") (pinfunction "IN_1") (pintype "power_in"))
    )
    (net (code "43") (name "Net-(U101-OUT)") (class "Default")
      (node (ref "C102") (pin "1") (pinfunction "1_1") (pintype "passive"))
      (node (ref "C5") (pin "1") (pinfunction "1_1") (pintype "passive"))
      (node (ref "JP8") (pin "13") (pinfunction "13_13") (pintype "passive"))
      (node (ref "JP8") (pin "14") (pinfunction "14_14") (pintype "passive"))
      (node (ref "U101") (pin "3") (pinfunction "OUT_3") (pintype "power_in"))
      (node (ref "U9") (pin "1") (pinfunction "Vcc1_1") (pintype "passive"))
    )
    (net (code "44") (name "Net-(U102-OUT)") (class "Default")
      (node (ref "C105") (pin "2") (pinfunction "2_2") (pintype "passive"))
      (node (ref "JP8") (pin "17") (pinfunction "17_17") (pintype "passive"))
      (node (ref "JP8") (pin "18") (pinfunction "18_18") (pintype "passive"))
      (node (ref "U102") (pin "1") (pinfunction "OUT_1") (pintype "power_in"))
    )
    (net (code "45") (name "Net-(U103-IN)") (class "Default")
      (node (ref "C107") (pin "1") (pinfunction "1_1") (pintype "passive"))
      (node (ref "L102") (pin "2") (pinfunction "2_2") (pintype "passive"))
      (node (ref "U103") (pin "8") (pinfunction "IN_8") (pintype "power_in"))
    )
    (net (code "46") (name "Net-(U103-NC-Pad4)") (class "Default")
      (node (ref "U103") (pin "4") (pinfunction "NC_4") (pintype "passive"))
      (node (ref "U103") (pin "5") (pinfunction "NC_5") (pintype "passive"))
    )
    (net (code "47") (name "Net-(U103-OUT)") (class "Default")
      (node (ref "C108") (pin "1") (pinfunction "1_1") (pintype "passive"))
      (node (ref "JP8") (pin "20") (pinfunction "20_20") (pintype "passive"))
      (node (ref "U103") (pin "1") (pinfunction "OUT_1") (pintype "power_in"))
    )
    (net (code "48") (name "unconnected-(J1-MH1-Pad10)") (class "Default")
      (node (ref "J1") (pin "10") (pinfunction "MH1_10") (pintype "passive"))
    )
    (net (code "49") (name "unconnected-(J1-MH2-Pad11)") (class "Default")
      (node (ref "J1") (pin "11") (pinfunction "MH2_11") (pintype "passive"))
    )
    (net (code "50") (name "unconnected-(J1-Pad5)") (class "Default")
      (node (ref "J1") (pin "5") (pinfunction "5_5") (pintype "passive"))
    )
    (net (code "51") (name "unconnected-(JP7-Pad7)") (class "Default")
      (node (ref "JP7") (pin "7") (pinfunction "7_7") (pintype "passive"))
    )
    (net (code "52") (name "unconnected-(JP7-Pad8)") (class "Default")
      (node (ref "JP7") (pin "8") (pinfunction "8_8") (pintype "passive"))
    )
    (net (code "53") (name "unconnected-(JP7-Pad9)") (class "Default")
      (node (ref "JP7") (pin "9") (pinfunction "9_9") (pintype "passive"))
    )
    (net (code "54") (name "unconnected-(JP7-Pad10)") (class "Default")
      (node (ref "JP7") (pin "10") (pinfunction "10_10") (pintype "passive"))
    )
    (net (code "55") (name "unconnected-(JP8-Pad9)") (class "Default")
      (node (ref "JP8") (pin "9") (pinfunction "9_9") (pintype "passive"))
    )
    (net (code "56") (name "unconnected-(JP8-Pad10)") (class "Default")
      (node (ref "JP8") (pin "10") (pinfunction "10_10") (pintype "passive"))
    )
    (net (code "57") (name "unconnected-(JP8-Pad11)") (class "Default")
      (node (ref "JP8") (pin "11") (pinfunction "11_11") (pintype "passive"))
    )
    (net (code "58") (name "unconnected-(JP8-Pad12)") (class "Default")
      (node (ref "JP8") (pin "12") (pinfunction "12_12") (pintype "passive"))
    )
    (net (code "59") (name "unconnected-(JP11-Pad9)") (class "Default")
      (node (ref "JP11") (pin "9") (pinfunction "9_9") (pintype "passive"))
    )
    (net (code "60") (name "unconnected-(JP11-Pad10)") (class "Default")
      (node (ref "JP11") (pin "10") (pinfunction "10_10") (pintype "passive"))
    )
    (net (code "61") (name "unconnected-(U102-NC-Pad4)") (class "Default")
      (node (ref "U102") (pin "4") (pinfunction "NC_4") (pintype "passive"))
    )
    (net (code "62") (name "unconnected-(U102-NC-Pad8)") (class "Default")
      (node (ref "U102") (pin "8") (pinfunction "NC_8") (pintype "passive"))
    )
  )
)
